# ADC3_60M.net
KiCad netlist of a schematic drawn in EAGLE
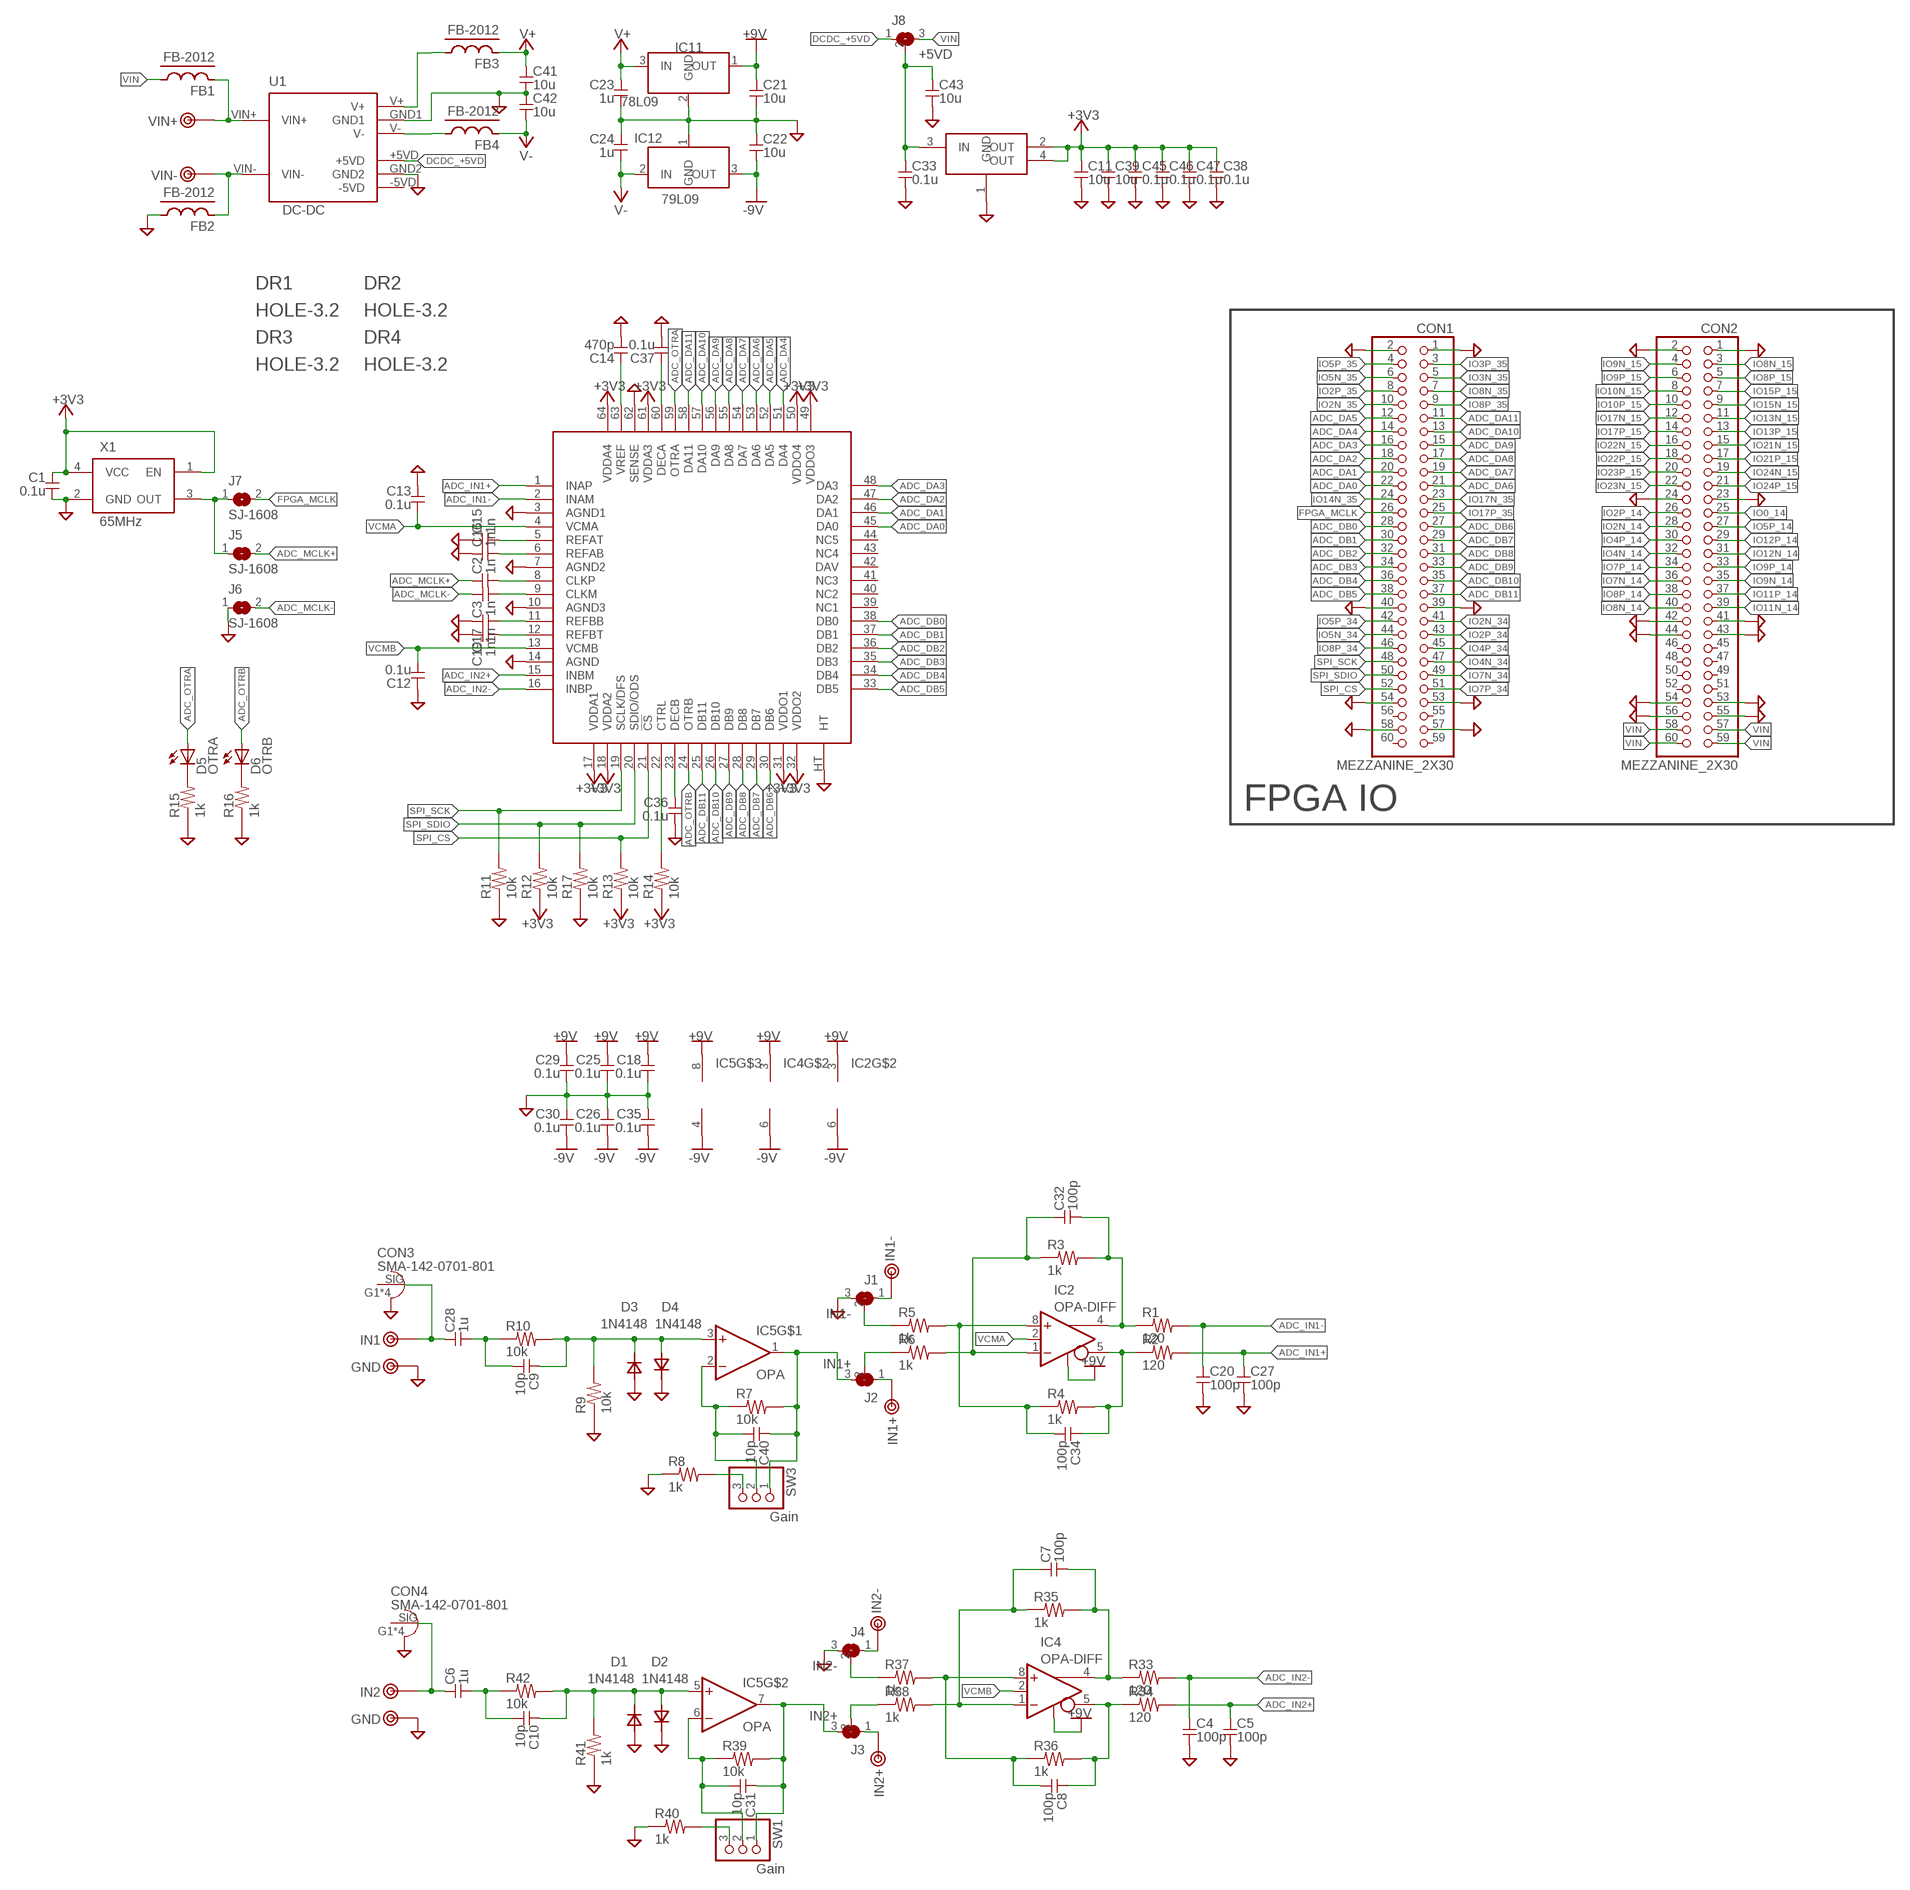
[diagram p0: schematic, sheet 1]

(export (version "E")
  (design (tool "Eeschema 10.0.6"))
  (components
    (comp (ref "C1")
      (value "0.1u")
      (footprint "eagle-import:1608")
      (libsource (lib "eagle-import") (part "C-1608"))
    )
    (comp (ref "C2")
      (value "1n")
      (footprint "eagle-import:1608")
      (libsource (lib "eagle-import") (part "C-1608"))
    )
    (comp (ref "C3")
      (value "1n")
      (footprint "eagle-import:1608")
      (libsource (lib "eagle-import") (part "C-1608"))
    )
    (comp (ref "C4")
      (value "100p")
      (footprint "eagle-import:1608")
      (libsource (lib "eagle-import") (part "C-1608"))
    )
    (comp (ref "C5")
      (value "100p")
      (footprint "eagle-import:1608")
      (libsource (lib "eagle-import") (part "C-1608"))
    )
    (comp (ref "C6")
      (value "1u")
      (footprint "eagle-import:C050")
      (libsource (lib "eagle-import") (part "C-5"))
    )
    (comp (ref "C7")
      (value "100p")
      (footprint "eagle-import:1608")
      (libsource (lib "eagle-import") (part "C-1608"))
    )
    (comp (ref "C8")
      (value "100p")
      (footprint "eagle-import:1608")
      (libsource (lib "eagle-import") (part "C-1608"))
    )
    (comp (ref "C9")
      (value "10p")
      (footprint "eagle-import:1608")
      (libsource (lib "eagle-import") (part "C-1608"))
    )
    (comp (ref "C10")
      (value "10p")
      (footprint "eagle-import:1608")
      (libsource (lib "eagle-import") (part "C-1608"))
    )
    (comp (ref "C11")
      (value "10u")
      (footprint "eagle-import:2012")
      (libsource (lib "eagle-import") (part "C-2012"))
    )
    (comp (ref "C12")
      (value "0.1u")
      (footprint "eagle-import:1608")
      (libsource (lib "eagle-import") (part "C-1608"))
    )
    (comp (ref "C13")
      (value "0.1u")
      (footprint "eagle-import:1608")
      (libsource (lib "eagle-import") (part "C-1608"))
    )
    (comp (ref "C14")
      (value "470p")
      (footprint "eagle-import:1608")
      (libsource (lib "eagle-import") (part "C-1608"))
    )
    (comp (ref "C15")
      (value "1n")
      (footprint "eagle-import:1608")
      (libsource (lib "eagle-import") (part "C-1608"))
    )
    (comp (ref "C16")
      (value "1n")
      (footprint "eagle-import:1608")
      (libsource (lib "eagle-import") (part "C-1608"))
    )
    (comp (ref "C17")
      (value "1n")
      (footprint "eagle-import:1608")
      (libsource (lib "eagle-import") (part "C-1608"))
    )
    (comp (ref "C18")
      (value "0.1u")
      (footprint "eagle-import:1608")
      (libsource (lib "eagle-import") (part "C-1608"))
    )
    (comp (ref "C19")
      (value "1n")
      (footprint "eagle-import:1608")
      (libsource (lib "eagle-import") (part "C-1608"))
    )
    (comp (ref "C20")
      (value "100p")
      (footprint "eagle-import:1608")
      (libsource (lib "eagle-import") (part "C-1608"))
    )
    (comp (ref "C21")
      (value "10u")
      (footprint "eagle-import:2012")
      (libsource (lib "eagle-import") (part "C-2012"))
    )
    (comp (ref "C22")
      (value "10u")
      (footprint "eagle-import:2012")
      (libsource (lib "eagle-import") (part "C-2012"))
    )
    (comp (ref "C23")
      (value "1u")
      (footprint "eagle-import:1608")
      (libsource (lib "eagle-import") (part "C-1608"))
    )
    (comp (ref "C24")
      (value "1u")
      (footprint "eagle-import:1608")
      (libsource (lib "eagle-import") (part "C-1608"))
    )
    (comp (ref "C25")
      (value "0.1u")
      (footprint "eagle-import:1608")
      (libsource (lib "eagle-import") (part "C-1608"))
    )
    (comp (ref "C26")
      (value "0.1u")
      (footprint "eagle-import:1608")
      (libsource (lib "eagle-import") (part "C-1608"))
    )
    (comp (ref "C27")
      (value "100p")
      (footprint "eagle-import:1608")
      (libsource (lib "eagle-import") (part "C-1608"))
    )
    (comp (ref "C28")
      (value "1u")
      (footprint "eagle-import:C050")
      (libsource (lib "eagle-import") (part "C-5"))
    )
    (comp (ref "C29")
      (value "0.1u")
      (footprint "eagle-import:1608")
      (libsource (lib "eagle-import") (part "C-1608"))
    )
    (comp (ref "C30")
      (value "0.1u")
      (footprint "eagle-import:1608")
      (libsource (lib "eagle-import") (part "C-1608"))
    )
    (comp (ref "C31")
      (value "10p")
      (footprint "eagle-import:1608")
      (libsource (lib "eagle-import") (part "C-1608"))
    )
    (comp (ref "C32")
      (value "100p")
      (footprint "eagle-import:1608")
      (libsource (lib "eagle-import") (part "C-1608"))
    )
    (comp (ref "C33")
      (value "0.1u")
      (footprint "eagle-import:1608")
      (libsource (lib "eagle-import") (part "C-1608"))
    )
    (comp (ref "C34")
      (value "100p")
      (footprint "eagle-import:1608")
      (libsource (lib "eagle-import") (part "C-1608"))
    )
    (comp (ref "C35")
      (value "0.1u")
      (footprint "eagle-import:1608")
      (libsource (lib "eagle-import") (part "C-1608"))
    )
    (comp (ref "C36")
      (value "0.1u")
      (footprint "eagle-import:1608")
      (libsource (lib "eagle-import") (part "C-1608"))
    )
    (comp (ref "C37")
      (value "0.1u")
      (footprint "eagle-import:1608")
      (libsource (lib "eagle-import") (part "C-1608"))
    )
    (comp (ref "C38")
      (value "0.1u")
      (footprint "eagle-import:1608")
      (libsource (lib "eagle-import") (part "C-1608"))
    )
    (comp (ref "C39")
      (value "10u")
      (footprint "eagle-import:2012")
      (libsource (lib "eagle-import") (part "C-2012"))
    )
    (comp (ref "C40")
      (value "10p")
      (footprint "eagle-import:1608")
      (libsource (lib "eagle-import") (part "C-1608"))
    )
    (comp (ref "C41")
      (value "10u")
      (footprint "eagle-import:3216")
      (libsource (lib "eagle-import") (part "C-3216"))
    )
    (comp (ref "C42")
      (value "10u")
      (footprint "eagle-import:3216")
      (libsource (lib "eagle-import") (part "C-3216"))
    )
    (comp (ref "C43")
      (value "10u")
      (footprint "eagle-import:2012")
      (libsource (lib "eagle-import") (part "C-2012"))
    )
    (comp (ref "C45")
      (value "0.1u")
      (footprint "eagle-import:1608")
      (libsource (lib "eagle-import") (part "C-1608"))
    )
    (comp (ref "C46")
      (value "0.1u")
      (footprint "eagle-import:1608")
      (libsource (lib "eagle-import") (part "C-1608"))
    )
    (comp (ref "C47")
      (value "0.1u")
      (footprint "eagle-import:1608")
      (libsource (lib "eagle-import") (part "C-1608"))
    )
    (comp (ref "CON1")
      (value "MEZZANINE_2X30")
      (footprint "eagle-import:MEZZANINE_0.8MM_2X30")
      (libsource (lib "eagle-import") (part "MEZZANINE_2X30"))
    )
    (comp (ref "CON2")
      (value "MEZZANINE_2X30")
      (footprint "eagle-import:MEZZANINE_0.8MM_2X30")
      (libsource (lib "eagle-import") (part "MEZZANINE_2X30"))
    )
    (comp (ref "CON3")
      (value "SMA-142-0701-801")
      (footprint "eagle-import:SMA-EDGE")
      (libsource (lib "eagle-import") (part "SMA-142-0701-801"))
    )
    (comp (ref "CON4")
      (value "SMA-142-0701-801")
      (footprint "eagle-import:SMA-EDGE")
      (libsource (lib "eagle-import") (part "SMA-142-0701-801"))
    )
    (comp (ref "D1")
      (value "1N4148")
      (footprint "eagle-import:SOD123")
      (libsource (lib "eagle-import") (part "DIODE-1N4148W"))
    )
    (comp (ref "D2")
      (value "1N4148")
      (footprint "eagle-import:SOD123")
      (libsource (lib "eagle-import") (part "DIODE-1N4148W"))
    )
    (comp (ref "D3")
      (value "1N4148")
      (footprint "eagle-import:SOD123")
      (libsource (lib "eagle-import") (part "DIODE-1N4148W"))
    )
    (comp (ref "D4")
      (value "1N4148")
      (footprint "eagle-import:SOD123")
      (libsource (lib "eagle-import") (part "DIODE-1N4148W"))
    )
    (comp (ref "D5")
      (value "OTRA")
      (footprint "eagle-import:D1608")
      (libsource (lib "eagle-import") (part "LED-SMD1608"))
    )
    (comp (ref "D6")
      (value "OTRB")
      (footprint "eagle-import:D1608")
      (libsource (lib "eagle-import") (part "LED-SMD1608"))
    )
    (comp (ref "DR1")
      (value "HOLE-3.2")
      (footprint "eagle-import:HOLE_3.2")
      (libsource (lib "eagle-import") (part "HOLE-3.2"))
    )
    (comp (ref "DR2")
      (value "HOLE-3.2")
      (footprint "eagle-import:HOLE_3.2")
      (libsource (lib "eagle-import") (part "HOLE-3.2"))
    )
    (comp (ref "DR3")
      (value "HOLE-3.2")
      (footprint "eagle-import:HOLE_3.2")
      (libsource (lib "eagle-import") (part "HOLE-3.2"))
    )
    (comp (ref "DR4")
      (value "HOLE-3.2")
      (footprint "eagle-import:HOLE_3.2")
      (libsource (lib "eagle-import") (part "HOLE-3.2"))
    )
    (comp (ref "FB1")
      (value "FB-2012")
      (footprint "eagle-import:2012-J")
      (libsource (lib "eagle-import") (part "FB-2012"))
    )
    (comp (ref "FB2")
      (value "FB-2012")
      (footprint "eagle-import:2012-J")
      (libsource (lib "eagle-import") (part "FB-2012"))
    )
    (comp (ref "FB3")
      (value "FB-2012")
      (footprint "eagle-import:2012-J")
      (libsource (lib "eagle-import") (part "FB-2012"))
    )
    (comp (ref "FB4")
      (value "FB-2012")
      (footprint "eagle-import:2012-J")
      (libsource (lib "eagle-import") (part "FB-2012"))
    )
    (comp (ref "IC1")
      (value "ADC1212")
      (footprint "eagle-import:QFN64HT")
      (libsource (lib "eagle-import") (part "ADC1212"))
    )
    (comp (ref "IC2")
      (value "OPA-DIFF")
      (footprint "eagle-import:SOP8")
      (libsource (lib "eagle-import") (part "OPA-DIFF"))
    )
    (comp (ref "IC4")
      (value "OPA-DIFF")
      (footprint "eagle-import:SOP8")
      (libsource (lib "eagle-import") (part "OPA-DIFF"))
    )
    (comp (ref "IC5")
      (value "OPA")
      (footprint "eagle-import:SOP8")
      (libsource (lib "eagle-import") (part "OPA-2-SOP"))
    )
    (comp (ref "IC7")
      (value "AZ1086H-3.3")
      (footprint "eagle-import:SOT223")
      (libsource (lib "eagle-import") (part "AZ1086?-H3.3"))
    )
    (comp (ref "IC11")
      (value "78L09")
      (footprint "eagle-import:TO-92")
      (libsource (lib "eagle-import") (part "78LX"))
    )
    (comp (ref "IC12")
      (value "79L09")
      (footprint "eagle-import:TO-92")
      (libsource (lib "eagle-import") (part "79LX"))
    )
    (comp (ref "J1")
      (value "IN1-")
      (footprint "eagle-import:1608-3-J")
      (libsource (lib "eagle-import") (part "SJ-3-1608"))
    )
    (comp (ref "J2")
      (value "IN1+")
      (footprint "eagle-import:1608-3-J")
      (libsource (lib "eagle-import") (part "SJ-3-1608"))
    )
    (comp (ref "J3")
      (value "IN2+")
      (footprint "eagle-import:1608-3-J")
      (libsource (lib "eagle-import") (part "SJ-3-1608"))
    )
    (comp (ref "J4")
      (value "IN2-")
      (footprint "eagle-import:1608-3-J")
      (libsource (lib "eagle-import") (part "SJ-3-1608"))
    )
    (comp (ref "J5")
      (value "SJ-1608")
      (footprint "eagle-import:1608-J")
      (libsource (lib "eagle-import") (part "SJ-1608"))
    )
    (comp (ref "J6")
      (value "SJ-1608")
      (footprint "eagle-import:1608-J")
      (libsource (lib "eagle-import") (part "SJ-1608"))
    )
    (comp (ref "J7")
      (value "SJ-1608")
      (footprint "eagle-import:1608-J")
      (libsource (lib "eagle-import") (part "SJ-1608"))
    )
    (comp (ref "J8")
      (value "+5VD")
      (footprint "eagle-import:2012-3-J")
      (libsource (lib "eagle-import") (part "SJ-3-2012"))
    )
    (comp (ref "R1")
      (value "120")
      (footprint "eagle-import:1608")
      (libsource (lib "eagle-import") (part "R-1608"))
    )
    (comp (ref "R2")
      (value "120")
      (footprint "eagle-import:1608")
      (libsource (lib "eagle-import") (part "R-1608"))
    )
    (comp (ref "R3")
      (value "1k")
      (footprint "eagle-import:1608")
      (libsource (lib "eagle-import") (part "R-1608"))
    )
    (comp (ref "R4")
      (value "1k")
      (footprint "eagle-import:1608")
      (libsource (lib "eagle-import") (part "R-1608"))
    )
    (comp (ref "R5")
      (value "1k")
      (footprint "eagle-import:1608")
      (libsource (lib "eagle-import") (part "R-1608"))
    )
    (comp (ref "R6")
      (value "1k")
      (footprint "eagle-import:1608")
      (libsource (lib "eagle-import") (part "R-1608"))
    )
    (comp (ref "R7")
      (value "10k")
      (footprint "eagle-import:1608")
      (libsource (lib "eagle-import") (part "R-1608"))
    )
    (comp (ref "R8")
      (value "1k")
      (footprint "eagle-import:1608")
      (libsource (lib "eagle-import") (part "R-1608"))
    )
    (comp (ref "R9")
      (value "10k")
      (footprint "eagle-import:1608")
      (libsource (lib "eagle-import") (part "R-1608"))
    )
    (comp (ref "R10")
      (value "10k")
      (footprint "eagle-import:1608")
      (libsource (lib "eagle-import") (part "R-1608"))
    )
    (comp (ref "R11")
      (value "10k")
      (footprint "eagle-import:1608")
      (libsource (lib "eagle-import") (part "R-1608"))
    )
    (comp (ref "R12")
      (value "10k")
      (footprint "eagle-import:1608")
      (libsource (lib "eagle-import") (part "R-1608"))
    )
    (comp (ref "R13")
      (value "10k")
      (footprint "eagle-import:1608")
      (libsource (lib "eagle-import") (part "R-1608"))
    )
    (comp (ref "R14")
      (value "10k")
      (footprint "eagle-import:1608")
      (libsource (lib "eagle-import") (part "R-1608"))
    )
    (comp (ref "R15")
      (value "1k")
      (footprint "eagle-import:1608")
      (libsource (lib "eagle-import") (part "R-1608"))
    )
    (comp (ref "R16")
      (value "1k")
      (footprint "eagle-import:1608")
      (libsource (lib "eagle-import") (part "R-1608"))
    )
    (comp (ref "R17")
      (value "10k")
      (footprint "eagle-import:1608")
      (libsource (lib "eagle-import") (part "R-1608"))
    )
    (comp (ref "R33")
      (value "120")
      (footprint "eagle-import:1608")
      (libsource (lib "eagle-import") (part "R-1608"))
    )
    (comp (ref "R34")
      (value "120")
      (footprint "eagle-import:1608")
      (libsource (lib "eagle-import") (part "R-1608"))
    )
    (comp (ref "R35")
      (value "1k")
      (footprint "eagle-import:1608")
      (libsource (lib "eagle-import") (part "R-1608"))
    )
    (comp (ref "R36")
      (value "1k")
      (footprint "eagle-import:1608")
      (libsource (lib "eagle-import") (part "R-1608"))
    )
    (comp (ref "R37")
      (value "1k")
      (footprint "eagle-import:1608")
      (libsource (lib "eagle-import") (part "R-1608"))
    )
    (comp (ref "R38")
      (value "1k")
      (footprint "eagle-import:1608")
      (libsource (lib "eagle-import") (part "R-1608"))
    )
    (comp (ref "R39")
      (value "10k")
      (footprint "eagle-import:1608")
      (libsource (lib "eagle-import") (part "R-1608"))
    )
    (comp (ref "R40")
      (value "1k")
      (footprint "eagle-import:1608")
      (libsource (lib "eagle-import") (part "R-1608"))
    )
    (comp (ref "R41")
      (value "1k")
      (footprint "eagle-import:1608")
      (libsource (lib "eagle-import") (part "R-1608"))
    )
    (comp (ref "R42")
      (value "10k")
      (footprint "eagle-import:1608")
      (libsource (lib "eagle-import") (part "R-1608"))
    )
    (comp (ref "SW1")
      (value "Gain")
      (footprint "eagle-import:1X03")
      (libsource (lib "eagle-import") (part "SW-1X3"))
    )
    (comp (ref "SW3")
      (value "Gain")
      (footprint "eagle-import:1X03")
      (libsource (lib "eagle-import") (part "SW-1X3"))
    )
    (comp (ref "TP1")
      (value "IN2")
      (footprint "eagle-import:TESTPIN")
      (libsource (lib "eagle-import") (part "TESTPIN"))
    )
    (comp (ref "TP2")
      (value "GND")
      (footprint "eagle-import:TESTPIN")
      (libsource (lib "eagle-import") (part "TESTPIN"))
    )
    (comp (ref "TP3")
      (value "IN2-")
      (footprint "eagle-import:TESTPIN")
      (libsource (lib "eagle-import") (part "TESTPIN"))
    )
    (comp (ref "TP4")
      (value "IN1")
      (footprint "eagle-import:TESTPIN")
      (libsource (lib "eagle-import") (part "TESTPIN"))
    )
    (comp (ref "TP5")
      (value "GND")
      (footprint "eagle-import:TESTPIN")
      (libsource (lib "eagle-import") (part "TESTPIN"))
    )
    (comp (ref "TP6")
      (value "IN2+")
      (footprint "eagle-import:TESTPIN")
      (libsource (lib "eagle-import") (part "TESTPIN"))
    )
    (comp (ref "TP7")
      (value "IN1-")
      (footprint "eagle-import:TESTPIN")
      (libsource (lib "eagle-import") (part "TESTPIN"))
    )
    (comp (ref "TP8")
      (value "IN1+")
      (footprint "eagle-import:TESTPIN")
      (libsource (lib "eagle-import") (part "TESTPIN"))
    )
    (comp (ref "TP30")
      (value "VIN+")
      (footprint "eagle-import:TESTPIN")
      (libsource (lib "eagle-import") (part "TESTPIN"))
    )
    (comp (ref "TP31")
      (value "VIN-")
      (footprint "eagle-import:TESTPIN")
      (libsource (lib "eagle-import") (part "TESTPIN"))
    )
    (comp (ref "U1")
      (value "DC-DC")
      (footprint "eagle-import:DCDC")
      (libsource (lib "eagle-import") (part "DC-DC"))
    )
    (comp (ref "X1")
      (value "65MHz")
      (footprint "eagle-import:KC3225")
      (libsource (lib "eagle-import") (part "OSC-KC3225"))
    )
  )
  (nets
    (net (code "1") (name "+3V3") (class "Default")
      (node (ref "C1") (pin "1") (pinfunction "1_1") (pintype "passive"))
      (node (ref "C11") (pin "1") (pinfunction "1_1") (pintype "passive"))
      (node (ref "C38") (pin "1") (pinfunction "1_1") (pintype "passive"))
      (node (ref "C39") (pin "1") (pinfunction "1_1") (pintype "passive"))
      (node (ref "C45") (pin "1") (pinfunction "1_1") (pintype "passive"))
      (node (ref "C46") (pin "1") (pinfunction "1_1") (pintype "passive"))
      (node (ref "C47") (pin "1") (pinfunction "1_1") (pintype "passive"))
      (node (ref "IC1") (pin "17") (pinfunction "VDDA1_17") (pintype "input"))
      (node (ref "IC1") (pin "18") (pinfunction "VDDA2_18") (pintype "input"))
      (node (ref "IC1") (pin "31") (pinfunction "VDDO1_31") (pintype "input"))
      (node (ref "IC1") (pin "32") (pinfunction "VDDO2_32") (pintype "input"))
      (node (ref "IC1") (pin "49") (pinfunction "VDDO3_49") (pintype "input"))
      (node (ref "IC1") (pin "50") (pinfunction "VDDO4_50") (pintype "input"))
      (node (ref "IC1") (pin "61") (pinfunction "VDDA3_61") (pintype "input"))
      (node (ref "IC1") (pin "64") (pinfunction "VDDA4_64") (pintype "input"))
      (node (ref "IC7") (pin "2") (pinfunction "OUT_2") (pintype "output"))
      (node (ref "IC7") (pin "4") (pinfunction "OUT_4") (pintype "output"))
      (node (ref "R12") (pin "1") (pinfunction "1_1") (pintype "passive"))
      (node (ref "R13") (pin "1") (pinfunction "1_1") (pintype "passive"))
      (node (ref "R14") (pin "1") (pinfunction "1_1") (pintype "passive"))
      (node (ref "X1") (pin "1") (pinfunction "EN_1") (pintype "input"))
      (node (ref "X1") (pin "4") (pinfunction "VCC_4") (pintype "input"))
    )
    (net (code "2") (name "+9V") (class "Default")
      (node (ref "C18") (pin "1") (pinfunction "1_1") (pintype "passive"))
      (node (ref "C21") (pin "1") (pinfunction "1_1") (pintype "passive"))
      (node (ref "C25") (pin "1") (pinfunction "1_1") (pintype "passive"))
      (node (ref "C29") (pin "1") (pinfunction "1_1") (pintype "passive"))
      (node (ref "IC11") (pin "1") (pinfunction "OUT_1") (pintype "output"))
      (node (ref "IC2") (pin "3") (pinfunction "V+_3") (pintype "power_in"))
      (node (ref "IC2") (pin "7") (pinfunction "EN_7") (pintype "bidirectional"))
      (node (ref "IC4") (pin "3") (pinfunction "V+_3") (pintype "power_in"))
      (node (ref "IC4") (pin "7") (pinfunction "EN_7") (pintype "bidirectional"))
      (node (ref "IC5") (pin "8") (pinfunction "V+_8") (pintype "power_in"))
    )
    (net (code "3") (name "-9V") (class "Default")
      (node (ref "C22") (pin "2") (pinfunction "2_2") (pintype "passive"))
      (node (ref "C26") (pin "2") (pinfunction "2_2") (pintype "passive"))
      (node (ref "C30") (pin "2") (pinfunction "2_2") (pintype "passive"))
      (node (ref "C35") (pin "2") (pinfunction "2_2") (pintype "passive"))
      (node (ref "IC12") (pin "3") (pinfunction "OUT_3") (pintype "output"))
      (node (ref "IC2") (pin "6") (pinfunction "V-_6") (pintype "power_in"))
      (node (ref "IC4") (pin "6") (pinfunction "V-_6") (pintype "power_in"))
      (node (ref "IC5") (pin "4") (pinfunction "V-_4") (pintype "power_in"))
    )
    (net (code "4") (name "ADC_DA0") (class "Default")
      (node (ref "CON1") (pin "22") (pinfunction "22_22") (pintype "passive"))
      (node (ref "IC1") (pin "45") (pinfunction "DA0_45") (pintype "output"))
    )
    (net (code "5") (name "ADC_DA1") (class "Default")
      (node (ref "CON1") (pin "20") (pinfunction "20_20") (pintype "passive"))
      (node (ref "IC1") (pin "46") (pinfunction "DA1_46") (pintype "output"))
    )
    (net (code "6") (name "ADC_DA2") (class "Default")
      (node (ref "CON1") (pin "18") (pinfunction "18_18") (pintype "passive"))
      (node (ref "IC1") (pin "47") (pinfunction "DA2_47") (pintype "output"))
    )
    (net (code "7") (name "ADC_DA3") (class "Default")
      (node (ref "CON1") (pin "16") (pinfunction "16_16") (pintype "passive"))
      (node (ref "IC1") (pin "48") (pinfunction "DA3_48") (pintype "output"))
    )
    (net (code "8") (name "ADC_DA4") (class "Default")
      (node (ref "CON1") (pin "14") (pinfunction "14_14") (pintype "passive"))
      (node (ref "IC1") (pin "51") (pinfunction "DA4_51") (pintype "output"))
    )
    (net (code "9") (name "ADC_DA5") (class "Default")
      (node (ref "CON1") (pin "12") (pinfunction "12_12") (pintype "passive"))
      (node (ref "IC1") (pin "52") (pinfunction "DA5_52") (pintype "output"))
    )
    (net (code "10") (name "ADC_DA6") (class "Default")
      (node (ref "CON1") (pin "21") (pinfunction "21_21") (pintype "passive"))
      (node (ref "IC1") (pin "53") (pinfunction "DA6_53") (pintype "output"))
    )
    (net (code "11") (name "ADC_DA7") (class "Default")
      (node (ref "CON1") (pin "19") (pinfunction "19_19") (pintype "passive"))
      (node (ref "IC1") (pin "54") (pinfunction "DA7_54") (pintype "output"))
    )
    (net (code "12") (name "ADC_DA8") (class "Default")
      (node (ref "CON1") (pin "17") (pinfunction "17_17") (pintype "passive"))
      (node (ref "IC1") (pin "55") (pinfunction "DA8_55") (pintype "output"))
    )
    (net (code "13") (name "ADC_DA9") (class "Default")
      (node (ref "CON1") (pin "15") (pinfunction "15_15") (pintype "passive"))
      (node (ref "IC1") (pin "56") (pinfunction "DA9_56") (pintype "output"))
    )
    (net (code "14") (name "ADC_DA10") (class "Default")
      (node (ref "CON1") (pin "13") (pinfunction "13_13") (pintype "passive"))
      (node (ref "IC1") (pin "57") (pinfunction "DA10_57") (pintype "output"))
    )
    (net (code "15") (name "ADC_DA11") (class "Default")
      (node (ref "CON1") (pin "11") (pinfunction "11_11") (pintype "passive"))
      (node (ref "IC1") (pin "58") (pinfunction "DA11_58") (pintype "output"))
    )
    (net (code "16") (name "ADC_DB0") (class "Default")
      (node (ref "CON1") (pin "28") (pinfunction "28_28") (pintype "passive"))
      (node (ref "IC1") (pin "38") (pinfunction "DB0_38") (pintype "output"))
    )
    (net (code "17") (name "ADC_DB1") (class "Default")
      (node (ref "CON1") (pin "30") (pinfunction "30_30") (pintype "passive"))
      (node (ref "IC1") (pin "37") (pinfunction "DB1_37") (pintype "output"))
    )
    (net (code "18") (name "ADC_DB2") (class "Default")
      (node (ref "CON1") (pin "32") (pinfunction "32_32") (pintype "passive"))
      (node (ref "IC1") (pin "36") (pinfunction "DB2_36") (pintype "output"))
    )
    (net (code "19") (name "ADC_DB3") (class "Default")
      (node (ref "CON1") (pin "34") (pinfunction "34_34") (pintype "passive"))
      (node (ref "IC1") (pin "35") (pinfunction "DB3_35") (pintype "output"))
    )
    (net (code "20") (name "ADC_DB4") (class "Default")
      (node (ref "CON1") (pin "36") (pinfunction "36_36") (pintype "passive"))
      (node (ref "IC1") (pin "34") (pinfunction "DB4_34") (pintype "output"))
    )
    (net (code "21") (name "ADC_DB5") (class "Default")
      (node (ref "CON1") (pin "38") (pinfunction "38_38") (pintype "passive"))
      (node (ref "IC1") (pin "33") (pinfunction "DB5_33") (pintype "output"))
    )
    (net (code "22") (name "ADC_DB6") (class "Default")
      (node (ref "CON1") (pin "27") (pinfunction "27_27") (pintype "passive"))
      (node (ref "IC1") (pin "30") (pinfunction "DB6_30") (pintype "output"))
    )
    (net (code "23") (name "ADC_DB7") (class "Default")
      (node (ref "CON1") (pin "29") (pinfunction "29_29") (pintype "passive"))
      (node (ref "IC1") (pin "29") (pinfunction "DB7_29") (pintype "output"))
    )
    (net (code "24") (name "ADC_DB8") (class "Default")
      (node (ref "CON1") (pin "31") (pinfunction "31_31") (pintype "passive"))
      (node (ref "IC1") (pin "28") (pinfunction "DB8_28") (pintype "output"))
    )
    (net (code "25") (name "ADC_DB9") (class "Default")
      (node (ref "CON1") (pin "33") (pinfunction "33_33") (pintype "passive"))
      (node (ref "IC1") (pin "27") (pinfunction "DB9_27") (pintype "output"))
    )
    (net (code "26") (name "ADC_DB10") (class "Default")
      (node (ref "CON1") (pin "35") (pinfunction "35_35") (pintype "passive"))
      (node (ref "IC1") (pin "26") (pinfunction "DB10_26") (pintype "output"))
    )
    (net (code "27") (name "ADC_DB11") (class "Default")
      (node (ref "CON1") (pin "37") (pinfunction "37_37") (pintype "passive"))
      (node (ref "IC1") (pin "25") (pinfunction "DB11_25") (pintype "output"))
    )
    (net (code "28") (name "ADC_IN1+") (class "Default")
      (node (ref "C27") (pin "1") (pinfunction "1_1") (pintype "passive"))
      (node (ref "IC1") (pin "1") (pinfunction "INAP_1") (pintype "input"))
      (node (ref "R2") (pin "2") (pinfunction "2_2") (pintype "passive"))
    )
    (net (code "29") (name "ADC_IN1-") (class "Default")
      (node (ref "C20") (pin "1") (pinfunction "1_1") (pintype "passive"))
      (node (ref "IC1") (pin "2") (pinfunction "INAM_2") (pintype "input"))
      (node (ref "R1") (pin "2") (pinfunction "2_2") (pintype "passive"))
    )
    (net (code "30") (name "ADC_IN2+") (class "Default")
      (node (ref "C5") (pin "1") (pinfunction "1_1") (pintype "passive"))
      (node (ref "IC1") (pin "15") (pinfunction "INBM_15") (pintype "input"))
      (node (ref "R34") (pin "2") (pinfunction "2_2") (pintype "passive"))
    )
    (net (code "31") (name "ADC_IN2-") (class "Default")
      (node (ref "C4") (pin "1") (pinfunction "1_1") (pintype "passive"))
      (node (ref "IC1") (pin "16") (pinfunction "INBP_16") (pintype "input"))
      (node (ref "R33") (pin "2") (pinfunction "2_2") (pintype "passive"))
    )
    (net (code "32") (name "ADC_MCLK+") (class "Default")
      (node (ref "C2") (pin "1") (pinfunction "1_1") (pintype "passive"))
      (node (ref "J5") (pin "2") (pinfunction "2_2") (pintype "passive"))
    )
    (net (code "33") (name "ADC_MCLK-") (class "Default")
      (node (ref "C3") (pin "1") (pinfunction "1_1") (pintype "passive"))
      (node (ref "J6") (pin "2") (pinfunction "2_2") (pintype "passive"))
    )
    (net (code "34") (name "ADC_OTRA") (class "Default")
      (node (ref "D5") (pin "A") (pinfunction "A_A") (pintype "passive"))
      (node (ref "IC1") (pin "59") (pinfunction "OTRA_59") (pintype "output"))
    )
    (net (code "35") (name "ADC_OTRB") (class "Default")
      (node (ref "D6") (pin "A") (pinfunction "A_A") (pintype "passive"))
      (node (ref "IC1") (pin "24") (pinfunction "OTRB_24") (pintype "output"))
    )
    (net (code "36") (name "DCDC_+5VD") (class "Default")
      (node (ref "J8") (pin "1") (pinfunction "1_1") (pintype "passive"))
      (node (ref "U1") (pin "+5VD") (pinfunction "+5VD_+5VD") (pintype "output"))
    )
    (net (code "37") (name "FPGA_MCLK") (class "Default")
      (node (ref "CON1") (pin "26") (pinfunction "26_26") (pintype "passive"))
      (node (ref "J7") (pin "2") (pinfunction "2_2") (pintype "passive"))
    )
    (net (code "38") (name "GND") (class "Default")
      (node (ref "C1") (pin "2") (pinfunction "2_2") (pintype "passive"))
      (node (ref "C11") (pin "2") (pinfunction "2_2") (pintype "passive"))
      (node (ref "C12") (pin "1") (pinfunction "1_1") (pintype "passive"))
      (node (ref "C13") (pin "1") (pinfunction "1_1") (pintype "passive"))
      (node (ref "C14") (pin "2") (pinfunction "2_2") (pintype "passive"))
      (node (ref "C15") (pin "1") (pinfunction "1_1") (pintype "passive"))
      (node (ref "C16") (pin "1") (pinfunction "1_1") (pintype "passive"))
      (node (ref "C17") (pin "1") (pinfunction "1_1") (pintype "passive"))
      (node (ref "C18") (pin "2") (pinfunction "2_2") (pintype "passive"))
      (node (ref "C19") (pin "1") (pinfunction "1_1") (pintype "passive"))
      (node (ref "C20") (pin "2") (pinfunction "2_2") (pintype "passive"))
      (node (ref "C21") (pin "2") (pinfunction "2_2") (pintype "passive"))
      (node (ref "C22") (pin "1") (pinfunction "1_1") (pintype "passive"))
      (node (ref "C23") (pin "2") (pinfunction "2_2") (pintype "passive"))
      (node (ref "C24") (pin "1") (pinfunction "1_1") (pintype "passive"))
      (node (ref "C25") (pin "2") (pinfunction "2_2") (pintype "passive"))
      (node (ref "C26") (pin "1") (pinfunction "1_1") (pintype "passive"))
      (node (ref "C27") (pin "2") (pinfunction "2_2") (pintype "passive"))
      (node (ref "C29") (pin "2") (pinfunction "2_2") (pintype "passive"))
      (node (ref "C30") (pin "1") (pinfunction "1_1") (pintype "passive"))
      (node (ref "C33") (pin "2") (pinfunction "2_2") (pintype "passive"))
      (node (ref "C35") (pin "1") (pinfunction "1_1") (pintype "passive"))
      (node (ref "C36") (pin "2") (pinfunction "2_2") (pintype "passive"))
      (node (ref "C37") (pin "2") (pinfunction "2_2") (pintype "passive"))
      (node (ref "C38") (pin "2") (pinfunction "2_2") (pintype "passive"))
      (node (ref "C39") (pin "2") (pinfunction "2_2") (pintype "passive"))
      (node (ref "C4") (pin "2") (pinfunction "2_2") (pintype "passive"))
      (node (ref "C41") (pin "2") (pinfunction "2_2") (pintype "passive"))
      (node (ref "C42") (pin "1") (pinfunction "1_1") (pintype "passive"))
      (node (ref "C43") (pin "2") (pinfunction "2_2") (pintype "passive"))
      (node (ref "C45") (pin "2") (pinfunction "2_2") (pintype "passive"))
      (node (ref "C46") (pin "2") (pinfunction "2_2") (pintype "passive"))
      (node (ref "C47") (pin "2") (pinfunction "2_2") (pintype "passive"))
      (node (ref "C5") (pin "2") (pinfunction "2_2") (pintype "passive"))
      (node (ref "CON1") (pin "1") (pinfunction "1_1") (pintype "passive"))
      (node (ref "CON1") (pin "2") (pinfunction "2_2") (pintype "passive"))
      (node (ref "CON1") (pin "39") (pinfunction "39_39") (pintype "passive"))
      (node (ref "CON1") (pin "40") (pinfunction "40_40") (pintype "passive"))
      (node (ref "CON1") (pin "53") (pinfunction "53_53") (pintype "passive"))
      (node (ref "CON1") (pin "54") (pinfunction "54_54") (pintype "passive"))
      (node (ref "CON1") (pin "57") (pinfunction "57_57") (pintype "passive"))
      (node (ref "CON1") (pin "58") (pinfunction "58_58") (pintype "passive"))
      (node (ref "CON2") (pin "1") (pinfunction "1_1") (pintype "passive"))
      (node (ref "CON2") (pin "2") (pinfunction "2_2") (pintype "passive"))
      (node (ref "CON2") (pin "23") (pinfunction "23_23") (pintype "passive"))
      (node (ref "CON2") (pin "24") (pinfunction "24_24") (pintype "passive"))
      (node (ref "CON2") (pin "41") (pinfunction "41_41") (pintype "passive"))
      (node (ref "CON2") (pin "42") (pinfunction "42_42") (pintype "passive"))
      (node (ref "CON2") (pin "43") (pinfunction "43_43") (pintype "passive"))
      (node (ref "CON2") (pin "44") (pinfunction "44_44") (pintype "passive"))
      (node (ref "CON2") (pin "53") (pinfunction "53_53") (pintype "passive"))
      (node (ref "CON2") (pin "54") (pinfunction "54_54") (pintype "passive"))
      (node (ref "CON2") (pin "55") (pinfunction "55_55") (pintype "passive"))
      (node (ref "CON2") (pin "56") (pinfunction "56_56") (pintype "passive"))
      (node (ref "CON3") (pin "G1") (pinfunction "GND_G1") (pintype "passive"))
      (node (ref "CON3") (pin "G2") (pinfunction "GND_G2") (pintype "passive"))
      (node (ref "CON3") (pin "G3") (pinfunction "GND_G3") (pintype "passive"))
      (node (ref "CON3") (pin "G4") (pinfunction "GND_G4") (pintype "passive"))
      (node (ref "CON4") (pin "G1") (pinfunction "GND_G1") (pintype "passive"))
      (node (ref "CON4") (pin "G2") (pinfunction "GND_G2") (pintype "passive"))
      (node (ref "CON4") (pin "G3") (pinfunction "GND_G3") (pintype "passive"))
      (node (ref "CON4") (pin "G4") (pinfunction "GND_G4") (pintype "passive"))
      (node (ref "D1") (pin "1") (pinfunction "A_1") (pintype "passive"))
      (node (ref "D2") (pin "2") (pinfunction "K_2") (pintype "passive"))
      (node (ref "D3") (pin "1") (pinfunction "A_1") (pintype "passive"))
      (node (ref "D4") (pin "2") (pinfunction "K_2") (pintype "passive"))
      (node (ref "FB2") (pin "1") (pinfunction "1_1") (pintype "passive"))
      (node (ref "IC1") (pin "10") (pinfunction "AGND3_10") (pintype "input"))
      (node (ref "IC1") (pin "14") (pinfunction "AGND_14") (pintype "input"))
      (node (ref "IC1") (pin "3") (pinfunction "AGND1_3") (pintype "input"))
      (node (ref "IC1") (pin "62") (pinfunction "SENSE_62") (pintype "input"))
      (node (ref "IC1") (pin "7") (pinfunction "AGND2_7") (pintype "input"))
      (node (ref "IC1") (pin "HT") (pinfunction "HT_HT") (pintype "passive"))
      (node (ref "IC11") (pin "2") (pinfunction "GND_2") (pintype "input"))
      (node (ref "IC12") (pin "1") (pinfunction "GND_1") (pintype "input"))
      (node (ref "IC7") (pin "1") (pinfunction "GND_1") (pintype "input"))
      (node (ref "J1") (pin "3") (pinfunction "3_3") (pintype "passive"))
      (node (ref "J4") (pin "3") (pinfunction "3_3") (pintype "passive"))
      (node (ref "J6") (pin "1") (pinfunction "1_1") (pintype "passive"))
      (node (ref "R11") (pin "1") (pinfunction "1_1") (pintype "passive"))
      (node (ref "R15") (pin "1") (pinfunction "1_1") (pintype "passive"))
      (node (ref "R16") (pin "1") (pinfunction "1_1") (pintype "passive"))
      (node (ref "R17") (pin "1") (pinfunction "1_1") (pintype "passive"))
      (node (ref "R40") (pin "1") (pinfunction "1_1") (pintype "passive"))
      (node (ref "R41") (pin "1") (pinfunction "1_1") (pintype "passive"))
      (node (ref "R8") (pin "1") (pinfunction "1_1") (pintype "passive"))
      (node (ref "R9") (pin "1") (pinfunction "1_1") (pintype "passive"))
      (node (ref "TP2") (pin "1") (pinfunction "1_1") (pintype "passive"))
      (node (ref "TP5") (pin "1") (pinfunction "1_1") (pintype "passive"))
      (node (ref "U1") (pin "GND1") (pinfunction "GND1_GND1") (pintype "power_in"))
      (node (ref "U1") (pin "GND2") (pinfunction "GND2_GND2") (pintype "power_in"))
      (node (ref "X1") (pin "2") (pinfunction "GND_2") (pintype "input"))
    )
    (net (code "39") (name "IO0_14") (class "Default")
      (node (ref "CON2") (pin "25") (pinfunction "25_25") (pintype "passive"))
    )
    (net (code "40") (name "IO2N_14") (class "Default")
      (node (ref "CON2") (pin "28") (pinfunction "28_28") (pintype "passive"))
    )
    (net (code "41") (name "IO2N_34") (class "Default")
      (node (ref "CON1") (pin "41") (pinfunction "41_41") (pintype "passive"))
    )
    (net (code "42") (name "IO2N_35") (class "Default")
      (node (ref "CON1") (pin "10") (pinfunction "10_10") (pintype "passive"))
    )
    (net (code "43") (name "IO2P_14") (class "Default")
      (node (ref "CON2") (pin "26") (pinfunction "26_26") (pintype "passive"))
    )
    (net (code "44") (name "IO2P_34") (class "Default")
      (node (ref "CON1") (pin "43") (pinfunction "43_43") (pintype "passive"))
    )
    (net (code "45") (name "IO2P_35") (class "Default")
      (node (ref "CON1") (pin "8") (pinfunction "8_8") (pintype "passive"))
    )
    (net (code "46") (name "IO3N_35") (class "Default")
      (node (ref "CON1") (pin "5") (pinfunction "5_5") (pintype "passive"))
    )
    (net (code "47") (name "IO3P_35") (class "Default")
      (node (ref "CON1") (pin "3") (pinfunction "3_3") (pintype "passive"))
    )
    (net (code "48") (name "IO4N_14") (class "Default")
      (node (ref "CON2") (pin "32") (pinfunction "32_32") (pintype "passive"))
    )
    (net (code "49") (name "IO4N_34") (class "Default")
      (node (ref "CON1") (pin "47") (pinfunction "47_47") (pintype "passive"))
    )
    (net (code "50") (name "IO4P_14") (class "Default")
      (node (ref "CON2") (pin "30") (pinfunction "30_30") (pintype "passive"))
    )
    (net (code "51") (name "IO4P_34") (class "Default")
      (node (ref "CON1") (pin "45") (pinfunction "45_45") (pintype "passive"))
    )
    (net (code "52") (name "IO5N_34") (class "Default")
      (node (ref "CON1") (pin "44") (pinfunction "44_44") (pintype "passive"))
    )
    (net (code "53") (name "IO5N_35") (class "Default")
      (node (ref "CON1") (pin "6") (pinfunction "6_6") (pintype "passive"))
    )
    (net (code "54") (name "IO5P_14") (class "Default")
      (node (ref "CON2") (pin "27") (pinfunction "27_27") (pintype "passive"))
    )
    (net (code "55") (name "IO5P_34") (class "Default")
      (node (ref "CON1") (pin "42") (pinfunction "42_42") (pintype "passive"))
    )
    (net (code "56") (name "IO5P_35") (class "Default")
      (node (ref "CON1") (pin "4") (pinfunction "4_4") (pintype "passive"))
    )
    (net (code "57") (name "IO7N_14") (class "Default")
      (node (ref "CON2") (pin "36") (pinfunction "36_36") (pintype "passive"))
    )
    (net (code "58") (name "IO7N_34") (class "Default")
      (node (ref "CON1") (pin "49") (pinfunction "49_49") (pintype "passive"))
    )
    (net (code "59") (name "IO7P_14") (class "Default")
      (node (ref "CON2") (pin "34") (pinfunction "34_34") (pintype "passive"))
    )
    (net (code "60") (name "IO7P_34") (class "Default")
      (node (ref "CON1") (pin "51") (pinfunction "51_51") (pintype "passive"))
    )
    (net (code "61") (name "IO8N_14") (class "Default")
      (node (ref "CON2") (pin "40") (pinfunction "40_40") (pintype "passive"))
    )
    (net (code "62") (name "IO8N_15") (class "Default")
      (node (ref "CON2") (pin "3") (pinfunction "3_3") (pintype "passive"))
    )
    (net (code "63") (name "IO8N_35") (class "Default")
      (node (ref "CON1") (pin "7") (pinfunction "7_7") (pintype "passive"))
    )
    (net (code "64") (name "IO8P_14") (class "Default")
      (node (ref "CON2") (pin "38") (pinfunction "38_38") (pintype "passive"))
    )
    (net (code "65") (name "IO8P_15") (class "Default")
      (node (ref "CON2") (pin "5") (pinfunction "5_5") (pintype "passive"))
    )
    (net (code "66") (name "IO8P_34") (class "Default")
      (node (ref "CON1") (pin "46") (pinfunction "46_46") (pintype "passive"))
    )
    (net (code "67") (name "IO8P_35") (class "Default")
      (node (ref "CON1") (pin "9") (pinfunction "9_9") (pintype "passive"))
    )
    (net (code "68") (name "IO9N_14") (class "Default")
      (node (ref "CON2") (pin "35") (pinfunction "35_35") (pintype "passive"))
    )
    (net (code "69") (name "IO9N_15") (class "Default")
      (node (ref "CON2") (pin "4") (pinfunction "4_4") (pintype "passive"))
    )
    (net (code "70") (name "IO9P_14") (class "Default")
      (node (ref "CON2") (pin "33") (pinfunction "33_33") (pintype "passive"))
    )
    (net (code "71") (name "IO9P_15") (class "Default")
      (node (ref "CON2") (pin "6") (pinfunction "6_6") (pintype "passive"))
    )
    (net (code "72") (name "IO10N_15") (class "Default")
      (node (ref "CON2") (pin "8") (pinfunction "8_8") (pintype "passive"))
    )
    (net (code "73") (name "IO10P_15") (class "Default")
      (node (ref "CON2") (pin "10") (pinfunction "10_10") (pintype "passive"))
    )
    (net (code "74") (name "IO11N_14") (class "Default")
      (node (ref "CON2") (pin "39") (pinfunction "39_39") (pintype "passive"))
    )
    (net (code "75") (name "IO11P_14") (class "Default")
      (node (ref "CON2") (pin "37") (pinfunction "37_37") (pintype "passive"))
    )
    (net (code "76") (name "IO12N_14") (class "Default")
      (node (ref "CON2") (pin "31") (pinfunction "31_31") (pintype "passive"))
    )
    (net (code "77") (name "IO12P_14") (class "Default")
      (node (ref "CON2") (pin "29") (pinfunction "29_29") (pintype "passive"))
    )
    (net (code "78") (name "IO13N_15") (class "Default")
      (node (ref "CON2") (pin "11") (pinfunction "11_11") (pintype "passive"))
    )
    (net (code "79") (name "IO13P_15") (class "Default")
      (node (ref "CON2") (pin "13") (pinfunction "13_13") (pintype "passive"))
    )
    (net (code "80") (name "IO14N_35") (class "Default")
      (node (ref "CON1") (pin "24") (pinfunction "24_24") (pintype "passive"))
    )
    (net (code "81") (name "IO15N_15") (class "Default")
      (node (ref "CON2") (pin "9") (pinfunction "9_9") (pintype "passive"))
    )
    (net (code "82") (name "IO15P_15") (class "Default")
      (node (ref "CON2") (pin "7") (pinfunction "7_7") (pintype "passive"))
    )
    (net (code "83") (name "IO17N_15") (class "Default")
      (node (ref "CON2") (pin "12") (pinfunction "12_12") (pintype "passive"))
    )
    (net (code "84") (name "IO17N_35") (class "Default")
      (node (ref "CON1") (pin "23") (pinfunction "23_23") (pintype "passive"))
    )
    (net (code "85") (name "IO17P_15") (class "Default")
      (node (ref "CON2") (pin "14") (pinfunction "14_14") (pintype "passive"))
    )
    (net (code "86") (name "IO17P_35") (class "Default")
      (node (ref "CON1") (pin "25") (pinfunction "25_25") (pintype "passive"))
    )
    (net (code "87") (name "IO21N_15") (class "Default")
      (node (ref "CON2") (pin "15") (pinfunction "15_15") (pintype "passive"))
    )
    (net (code "88") (name "IO21P_15") (class "Default")
      (node (ref "CON2") (pin "17") (pinfunction "17_17") (pintype "passive"))
    )
    (net (code "89") (name "IO22N_15") (class "Default")
      (node (ref "CON2") (pin "16") (pinfunction "16_16") (pintype "passive"))
    )
    (net (code "90") (name "IO22P_15") (class "Default")
      (node (ref "CON2") (pin "18") (pinfunction "18_18") (pintype "passive"))
    )
    (net (code "91") (name "IO23N_15") (class "Default")
      (node (ref "CON2") (pin "22") (pinfunction "22_22") (pintype "passive"))
    )
    (net (code "92") (name "IO23P_15") (class "Default")
      (node (ref "CON2") (pin "20") (pinfunction "20_20") (pintype "passive"))
    )
    (net (code "93") (name "IO24N_15") (class "Default")
      (node (ref "CON2") (pin "19") (pinfunction "19_19") (pintype "passive"))
    )
    (net (code "94") (name "IO24P_15") (class "Default")
      (node (ref "CON2") (pin "21") (pinfunction "21_21") (pintype "passive"))
    )
    (net (code "95") (name "Net-(C6-Pad1)") (class "Default")
      (node (ref "C6") (pin "1") (pinfunction "1_1") (pintype "passive"))
      (node (ref "CON4") (pin "SIG") (pinfunction "SIG_SIG") (pintype "passive"))
      (node (ref "TP1") (pin "1") (pinfunction "1_1") (pintype "passive"))
    )
    (net (code "96") (name "Net-(C10-Pad2)") (class "Default")
      (node (ref "C10") (pin "2") (pinfunction "2_2") (pintype "passive"))
      (node (ref "C6") (pin "2") (pinfunction "2_2") (pintype "passive"))
      (node (ref "R42") (pin "1") (pinfunction "1_1") (pintype "passive"))
    )
    (net (code "97") (name "Net-(C28-Pad1)") (class "Default")
      (node (ref "C28") (pin "1") (pinfunction "1_1") (pintype "passive"))
      (node (ref "CON3") (pin "SIG") (pinfunction "SIG_SIG") (pintype "passive"))
      (node (ref "TP4") (pin "1") (pinfunction "1_1") (pintype "passive"))
    )
    (net (code "98") (name "Net-(C28-Pad2)") (class "Default")
      (node (ref "C28") (pin "2") (pinfunction "2_2") (pintype "passive"))
      (node (ref "C9") (pin "2") (pinfunction "2_2") (pintype "passive"))
      (node (ref "R10") (pin "1") (pinfunction "1_1") (pintype "passive"))
    )
    (net (code "99") (name "Net-(D1-K)") (class "Default")
      (node (ref "C10") (pin "1") (pinfunction "1_1") (pintype "passive"))
      (node (ref "D1") (pin "2") (pinfunction "K_2") (pintype "passive"))
      (node (ref "D2") (pin "1") (pinfunction "A_1") (pintype "passive"))
      (node (ref "IC5") (pin "5") (pinfunction "+IN_5") (pintype "input"))
      (node (ref "R41") (pin "2") (pinfunction "2_2") (pintype "passive"))
      (node (ref "R42") (pin "2") (pinfunction "2_2") (pintype "passive"))
    )
    (net (code "100") (name "Net-(D3-K)") (class "Default")
      (node (ref "C9") (pin "1") (pinfunction "1_1") (pintype "passive"))
      (node (ref "D3") (pin "2") (pinfunction "K_2") (pintype "passive"))
      (node (ref "D4") (pin "1") (pinfunction "A_1") (pintype "passive"))
      (node (ref "IC5") (pin "3") (pinfunction "+IN_3") (pintype "input"))
      (node (ref "R10") (pin "2") (pinfunction "2_2") (pintype "passive"))
      (node (ref "R9") (pin "2") (pinfunction "2_2") (pintype "passive"))
    )
    (net (code "101") (name "Net-(D5-PadK)") (class "Default")
      (node (ref "D5") (pin "K") (pinfunction "K_K") (pintype "passive"))
      (node (ref "R15") (pin "2") (pinfunction "2_2") (pintype "passive"))
    )
    (net (code "102") (name "Net-(D6-PadK)") (class "Default")
      (node (ref "D6") (pin "K") (pinfunction "K_K") (pintype "passive"))
      (node (ref "R16") (pin "2") (pinfunction "2_2") (pintype "passive"))
    )
    (net (code "103") (name "Net-(FB1-Pad2)") (class "Default")
      (node (ref "FB1") (pin "2") (pinfunction "2_2") (pintype "passive"))
      (node (ref "TP30") (pin "1") (pinfunction "1_1") (pintype "passive"))
      (node (ref "U1") (pin "VIN+") (pinfunction "VIN+_VIN+") (pintype "power_in"))
    )
    (net (code "104") (name "Net-(FB2-Pad2)") (class "Default")
      (node (ref "FB2") (pin "2") (pinfunction "2_2") (pintype "passive"))
      (node (ref "TP31") (pin "1") (pinfunction "1_1") (pintype "passive"))
      (node (ref "U1") (pin "VIN-") (pinfunction "VIN-_VIN-") (pintype "power_in"))
    )
    (net (code "105") (name "Net-(FB3-Pad1)") (class "Default")
      (node (ref "FB3") (pin "1") (pinfunction "1_1") (pintype "passive"))
      (node (ref "U1") (pin "V+") (pinfunction "V+_V+") (pintype "output"))
    )
    (net (code "106") (name "Net-(FB4-Pad1)") (class "Default")
      (node (ref "FB4") (pin "1") (pinfunction "1_1") (pintype "passive"))
      (node (ref "U1") (pin "V-") (pinfunction "V-_V-") (pintype "output"))
    )
    (net (code "107") (name "Net-(IC1-CLKM)") (class "Default")
      (node (ref "C3") (pin "2") (pinfunction "2_2") (pintype "passive"))
      (node (ref "IC1") (pin "9") (pinfunction "CLKM_9") (pintype "input"))
    )
    (net (code "108") (name "Net-(IC1-CLKP)") (class "Default")
      (node (ref "C2") (pin "2") (pinfunction "2_2") (pintype "passive"))
      (node (ref "IC1") (pin "8") (pinfunction "CLKP_8") (pintype "input"))
    )
    (net (code "109") (name "Net-(IC1-CTRL)") (class "Default")
      (node (ref "IC1") (pin "22") (pinfunction "CTRL_22") (pintype "input"))
      (node (ref "R14") (pin "2") (pinfunction "2_2") (pintype "passive"))
    )
    (net (code "110") (name "Net-(IC1-DECA)") (class "Default")
      (node (ref "C37") (pin "1") (pinfunction "1_1") (pintype "passive"))
      (node (ref "IC1") (pin "60") (pinfunction "DECA_60") (pintype "output"))
    )
    (net (code "111") (name "Net-(IC1-DECB)") (class "Default")
      (node (ref "C36") (pin "1") (pinfunction "1_1") (pintype "passive"))
      (node (ref "IC1") (pin "23") (pinfunction "DECB_23") (pintype "output"))
    )
    (net (code "112") (name "Net-(IC1-REFAB)") (class "Default")
      (node (ref "C16") (pin "2") (pinfunction "2_2") (pintype "passive"))
      (node (ref "IC1") (pin "6") (pinfunction "REFAB_6") (pintype "output"))
    )
    (net (code "113") (name "Net-(IC1-REFAT)") (class "Default")
      (node (ref "C15") (pin "2") (pinfunction "2_2") (pintype "passive"))
      (node (ref "IC1") (pin "5") (pinfunction "REFAT_5") (pintype "output"))
    )
    (net (code "114") (name "Net-(IC1-REFBB)") (class "Default")
      (node (ref "C17") (pin "2") (pinfunction "2_2") (pintype "passive"))
      (node (ref "IC1") (pin "11") (pinfunction "REFBB_11") (pintype "output"))
    )
    (net (code "115") (name "Net-(IC1-REFBT)") (class "Default")
      (node (ref "C19") (pin "2") (pinfunction "2_2") (pintype "passive"))
      (node (ref "IC1") (pin "12") (pinfunction "REFBT_12") (pintype "input"))
    )
    (net (code "116") (name "Net-(IC1-VREF)") (class "Default")
      (node (ref "C14") (pin "1") (pinfunction "1_1") (pintype "passive"))
      (node (ref "IC1") (pin "63") (pinfunction "VREF_63") (pintype "input"))
    )
    (net (code "117") (name "Net-(IC2A-+IN)") (class "Default")
      (node (ref "C34") (pin "2") (pinfunction "2_2") (pintype "passive"))
      (node (ref "IC2") (pin "8") (pinfunction "+IN_8") (pintype "input"))
      (node (ref "R4") (pin "1") (pinfunction "1_1") (pintype "passive"))
      (node (ref "R5") (pin "2") (pinfunction "2_2") (pintype "passive"))
    )
    (net (code "118") (name "Net-(IC2A-+OUT)") (class "Default")
      (node (ref "C32") (pin "2") (pinfunction "2_2") (pintype "passive"))
      (node (ref "IC2") (pin "4") (pinfunction "+OUT_4") (pintype "output"))
      (node (ref "R1") (pin "1") (pinfunction "1_1") (pintype "passive"))
      (node (ref "R3") (pin "2") (pinfunction "2_2") (pintype "passive"))
    )
    (net (code "119") (name "Net-(IC2A--IN)") (class "Default")
      (node (ref "C32") (pin "1") (pinfunction "1_1") (pintype "passive"))
      (node (ref "IC2") (pin "1") (pinfunction "-IN_1") (pintype "input"))
      (node (ref "R3") (pin "1") (pinfunction "1_1") (pintype "passive"))
      (node (ref "R6") (pin "2") (pinfunction "2_2") (pintype "passive"))
    )
    (net (code "120") (name "Net-(IC2A--OUT)") (class "Default")
      (node (ref "C34") (pin "1") (pinfunction "1_1") (pintype "passive"))
      (node (ref "IC2") (pin "5") (pinfunction "-OUT_5") (pintype "output"))
      (node (ref "R2") (pin "1") (pinfunction "1_1") (pintype "passive"))
      (node (ref "R4") (pin "2") (pinfunction "2_2") (pintype "passive"))
    )
    (net (code "121") (name "Net-(IC4A-+IN)") (class "Default")
      (node (ref "C8") (pin "2") (pinfunction "2_2") (pintype "passive"))
      (node (ref "IC4") (pin "8") (pinfunction "+IN_8") (pintype "input"))
      (node (ref "R36") (pin "1") (pinfunction "1_1") (pintype "passive"))
      (node (ref "R37") (pin "2") (pinfunction "2_2") (pintype "passive"))
    )
    (net (code "122") (name "Net-(IC4A-+OUT)") (class "Default")
      (node (ref "C7") (pin "2") (pinfunction "2_2") (pintype "passive"))
      (node (ref "IC4") (pin "4") (pinfunction "+OUT_4") (pintype "output"))
      (node (ref "R33") (pin "1") (pinfunction "1_1") (pintype "passive"))
      (node (ref "R35") (pin "2") (pinfunction "2_2") (pintype "passive"))
    )
    (net (code "123") (name "Net-(IC4A--IN)") (class "Default")
      (node (ref "C7") (pin "1") (pinfunction "1_1") (pintype "passive"))
      (node (ref "IC4") (pin "1") (pinfunction "-IN_1") (pintype "input"))
      (node (ref "R35") (pin "1") (pinfunction "1_1") (pintype "passive"))
      (node (ref "R38") (pin "2") (pinfunction "2_2") (pintype "passive"))
    )
    (net (code "124") (name "Net-(IC4A--OUT)") (class "Default")
      (node (ref "C8") (pin "1") (pinfunction "1_1") (pintype "passive"))
      (node (ref "IC4") (pin "5") (pinfunction "-OUT_5") (pintype "output"))
      (node (ref "R34") (pin "1") (pinfunction "1_1") (pintype "passive"))
      (node (ref "R36") (pin "2") (pinfunction "2_2") (pintype "passive"))
    )
    (net (code "125") (name "Net-(IC5A--IN)") (class "Default")
      (node (ref "C40") (pin "2") (pinfunction "2_2") (pintype "passive"))
      (node (ref "IC5") (pin "2") (pinfunction "-IN_2") (pintype "input"))
      (node (ref "R7") (pin "1") (pinfunction "1_1") (pintype "passive"))
      (node (ref "SW3") (pin "2") (pinfunction "2_2") (pintype "passive"))
    )
    (net (code "126") (name "Net-(IC5A-OUT)") (class "Default")
      (node (ref "C40") (pin "1") (pinfunction "1_1") (pintype "passive"))
      (node (ref "IC5") (pin "1") (pinfunction "OUT_1") (pintype "output"))
      (node (ref "J2") (pin "3") (pinfunction "3_3") (pintype "passive"))
      (node (ref "R7") (pin "2") (pinfunction "2_2") (pintype "passive"))
      (node (ref "SW3") (pin "1") (pinfunction "1_1") (pintype "passive"))
    )
    (net (code "127") (name "Net-(IC5B--IN)") (class "Default")
      (node (ref "C31") (pin "2") (pinfunction "2_2") (pintype "passive"))
      (node (ref "IC5") (pin "6") (pinfunction "-IN_6") (pintype "input"))
      (node (ref "R39") (pin "1") (pinfunction "1_1") (pintype "passive"))
      (node (ref "SW1") (pin "2") (pinfunction "2_2") (pintype "passive"))
    )
    (net (code "128") (name "Net-(IC5B-OUT)") (class "Default")
      (node (ref "C31") (pin "1") (pinfunction "1_1") (pintype "passive"))
      (node (ref "IC5") (pin "7") (pinfunction "OUT_7") (pintype "output"))
      (node (ref "J3") (pin "3") (pinfunction "3_3") (pintype "passive"))
      (node (ref "R39") (pin "2") (pinfunction "2_2") (pintype "passive"))
      (node (ref "SW1") (pin "1") (pinfunction "1_1") (pintype "passive"))
    )
    (net (code "129") (name "Net-(IC7-IN)") (class "Default")
      (node (ref "C33") (pin "1") (pinfunction "1_1") (pintype "passive"))
      (node (ref "C43") (pin "1") (pinfunction "1_1") (pintype "passive"))
      (node (ref "IC7") (pin "3") (pinfunction "IN_3") (pintype "input"))
      (node (ref "J8") (pin "2") (pinfunction "2_2") (pintype "passive"))
    )
    (net (code "130") (name "Net-(J1-Pad1)") (class "Default")
      (node (ref "J1") (pin "1") (pinfunction "1_1") (pintype "passive"))
      (node (ref "TP7") (pin "1") (pinfunction "1_1") (pintype "passive"))
    )
    (net (code "131") (name "Net-(J1-Pad2)") (class "Default")
      (node (ref "J1") (pin "2") (pinfunction "2_2") (pintype "passive"))
      (node (ref "R5") (pin "1") (pinfunction "1_1") (pintype "passive"))
    )
    (net (code "132") (name "Net-(J2-Pad1)") (class "Default")
      (node (ref "J2") (pin "1") (pinfunction "1_1") (pintype "passive"))
      (node (ref "TP8") (pin "1") (pinfunction "1_1") (pintype "passive"))
    )
    (net (code "133") (name "Net-(J2-Pad2)") (class "Default")
      (node (ref "J2") (pin "2") (pinfunction "2_2") (pintype "passive"))
      (node (ref "R6") (pin "1") (pinfunction "1_1") (pintype "passive"))
    )
    (net (code "134") (name "Net-(J3-Pad1)") (class "Default")
      (node (ref "J3") (pin "1") (pinfunction "1_1") (pintype "passive"))
      (node (ref "TP6") (pin "1") (pinfunction "1_1") (pintype "passive"))
    )
    (net (code "135") (name "Net-(J3-Pad2)") (class "Default")
      (node (ref "J3") (pin "2") (pinfunction "2_2") (pintype "passive"))
      (node (ref "R38") (pin "1") (pinfunction "1_1") (pintype "passive"))
    )
    (net (code "136") (name "Net-(J4-Pad1)") (class "Default")
      (node (ref "J4") (pin "1") (pinfunction "1_1") (pintype "passive"))
      (node (ref "TP3") (pin "1") (pinfunction "1_1") (pintype "passive"))
    )
    (net (code "137") (name "Net-(J4-Pad2)") (class "Default")
      (node (ref "J4") (pin "2") (pinfunction "2_2") (pintype "passive"))
      (node (ref "R37") (pin "1") (pinfunction "1_1") (pintype "passive"))
    )
    (net (code "138") (name "Net-(R8-Pad2)") (class "Default")
      (node (ref "R8") (pin "2") (pinfunction "2_2") (pintype "passive"))
      (node (ref "SW3") (pin "3") (pinfunction "3_3") (pintype "passive"))
    )
    (net (code "139") (name "Net-(R40-Pad2)") (class "Default")
      (node (ref "R40") (pin "2") (pinfunction "2_2") (pintype "passive"))
      (node (ref "SW1") (pin "3") (pinfunction "3_3") (pintype "passive"))
    )
    (net (code "140") (name "Net-(X1-OUT)") (class "Default")
      (node (ref "J5") (pin "1") (pinfunction "1_1") (pintype "passive"))
      (node (ref "J7") (pin "1") (pinfunction "1_1") (pintype "passive"))
      (node (ref "X1") (pin "3") (pinfunction "OUT_3") (pintype "output"))
    )
    (net (code "141") (name "SPI_CS") (class "Default")
      (node (ref "CON1") (pin "52") (pinfunction "52_52") (pintype "passive"))
      (node (ref "IC1") (pin "21") (pinfunction "~{CS}_21") (pintype "input"))
      (node (ref "R13") (pin "2") (pinfunction "2_2") (pintype "passive"))
    )
    (net (code "142") (name "SPI_SCK") (class "Default")
      (node (ref "CON1") (pin "48") (pinfunction "48_48") (pintype "passive"))
      (node (ref "IC1") (pin "19") (pinfunction "SCLK/DFS_19") (pintype "input"))
      (node (ref "R11") (pin "2") (pinfunction "2_2") (pintype "passive"))
    )
    (net (code "143") (name "SPI_SDIO") (class "Default")
      (node (ref "CON1") (pin "50") (pinfunction "50_50") (pintype "passive"))
      (node (ref "IC1") (pin "20") (pinfunction "SDIO/ODS_20") (pintype "bidirectional"))
      (node (ref "R12") (pin "2") (pinfunction "2_2") (pintype "passive"))
      (node (ref "R17") (pin "2") (pinfunction "2_2") (pintype "passive"))
    )
    (net (code "144") (name "V+") (class "Default")
      (node (ref "C23") (pin "1") (pinfunction "1_1") (pintype "passive"))
      (node (ref "C41") (pin "1") (pinfunction "1_1") (pintype "passive"))
      (node (ref "FB3") (pin "2") (pinfunction "2_2") (pintype "passive"))
      (node (ref "IC11") (pin "3") (pinfunction "IN_3") (pintype "input"))
    )
    (net (code "145") (name "V-") (class "Default")
      (node (ref "C24") (pin "2") (pinfunction "2_2") (pintype "passive"))
      (node (ref "C42") (pin "2") (pinfunction "2_2") (pintype "passive"))
      (node (ref "FB4") (pin "2") (pinfunction "2_2") (pintype "passive"))
      (node (ref "IC12") (pin "2") (pinfunction "IN_2") (pintype "input"))
    )
    (net (code "146") (name "VCMA") (class "Default")
      (node (ref "C13") (pin "2") (pinfunction "2_2") (pintype "passive"))
      (node (ref "IC1") (pin "4") (pinfunction "VCMA_4") (pintype "output"))
      (node (ref "IC2") (pin "2") (pinfunction "CM_2") (pintype "input"))
    )
    (net (code "147") (name "VCMB") (class "Default")
      (node (ref "C12") (pin "2") (pinfunction "2_2") (pintype "passive"))
      (node (ref "IC1") (pin "13") (pinfunction "VCMB_13") (pintype "output"))
      (node (ref "IC4") (pin "2") (pinfunction "CM_2") (pintype "input"))
    )
    (net (code "148") (name "VIN") (class "Default")
      (node (ref "CON2") (pin "57") (pinfunction "57_57") (pintype "passive"))
      (node (ref "CON2") (pin "58") (pinfunction "58_58") (pintype "passive"))
      (node (ref "CON2") (pin "59") (pinfunction "59_59") (pintype "passive"))
      (node (ref "CON2") (pin "60") (pinfunction "60_60") (pintype "passive"))
      (node (ref "FB1") (pin "1") (pinfunction "1_1") (pintype "passive"))
      (node (ref "J8") (pin "3") (pinfunction "3_3") (pintype "passive"))
    )
    (net (code "149") (name "unconnected-(CON1-Pad55)") (class "Default")
      (node (ref "CON1") (pin "55") (pinfunction "55_55") (pintype "passive"))
    )
    (net (code "150") (name "unconnected-(CON1-Pad56)") (class "Default")
      (node (ref "CON1") (pin "56") (pinfunction "56_56") (pintype "passive"))
    )
    (net (code "151") (name "unconnected-(CON1-Pad59)") (class "Default")
      (node (ref "CON1") (pin "59") (pinfunction "59_59") (pintype "passive"))
    )
    (net (code "152") (name "unconnected-(CON1-Pad60)") (class "Default")
      (node (ref "CON1") (pin "60") (pinfunction "60_60") (pintype "passive"))
    )
    (net (code "153") (name "unconnected-(CON2-Pad45)") (class "Default")
      (node (ref "CON2") (pin "45") (pinfunction "45_45") (pintype "passive"))
    )
    (net (code "154") (name "unconnected-(CON2-Pad46)") (class "Default")
      (node (ref "CON2") (pin "46") (pinfunction "46_46") (pintype "passive"))
    )
    (net (code "155") (name "unconnected-(CON2-Pad47)") (class "Default")
      (node (ref "CON2") (pin "47") (pinfunction "47_47") (pintype "passive"))
    )
    (net (code "156") (name "unconnected-(CON2-Pad48)") (class "Default")
      (node (ref "CON2") (pin "48") (pinfunction "48_48") (pintype "passive"))
    )
    (net (code "157") (name "unconnected-(CON2-Pad49)") (class "Default")
      (node (ref "CON2") (pin "49") (pinfunction "49_49") (pintype "passive"))
    )
    (net (code "158") (name "unconnected-(CON2-Pad50)") (class "Default")
      (node (ref "CON2") (pin "50") (pinfunction "50_50") (pintype "passive"))
    )
    (net (code "159") (name "unconnected-(CON2-Pad51)") (class "Default")
      (node (ref "CON2") (pin "51") (pinfunction "51_51") (pintype "passive"))
    )
    (net (code "160") (name "unconnected-(CON2-Pad52)") (class "Default")
      (node (ref "CON2") (pin "52") (pinfunction "52_52") (pintype "passive"))
    )
    (net (code "161") (name "unconnected-(IC1-DAV-Pad42)") (class "Default")
      (node (ref "IC1") (pin "42") (pinfunction "DAV_42") (pintype "output"))
    )
    (net (code "162") (name "unconnected-(IC1-NC1-Pad39)") (class "Default")
      (node (ref "IC1") (pin "39") (pinfunction "NC1_39") (pintype "passive"))
    )
    (net (code "163") (name "unconnected-(IC1-NC2-Pad40)") (class "Default")
      (node (ref "IC1") (pin "40") (pinfunction "NC2_40") (pintype "passive"))
    )
    (net (code "164") (name "unconnected-(IC1-NC3-Pad41)") (class "Default")
      (node (ref "IC1") (pin "41") (pinfunction "NC3_41") (pintype "passive"))
    )
    (net (code "165") (name "unconnected-(IC1-NC4-Pad43)") (class "Default")
      (node (ref "IC1") (pin "43") (pinfunction "NC4_43") (pintype "passive"))
    )
    (net (code "166") (name "unconnected-(IC1-NC5-Pad44)") (class "Default")
      (node (ref "IC1") (pin "44") (pinfunction "NC5_44") (pintype "passive"))
    )
    (net (code "167") (name "unconnected-(U1-Pad-5VD)") (class "Default")
      (node (ref "U1") (pin "-5VD") (pinfunction "-5VD_-5VD") (pintype "output"))
    )
  )
)
